# Fri3D_2018_00.net
KiCad netlist of a schematic drawn in Altium Designer
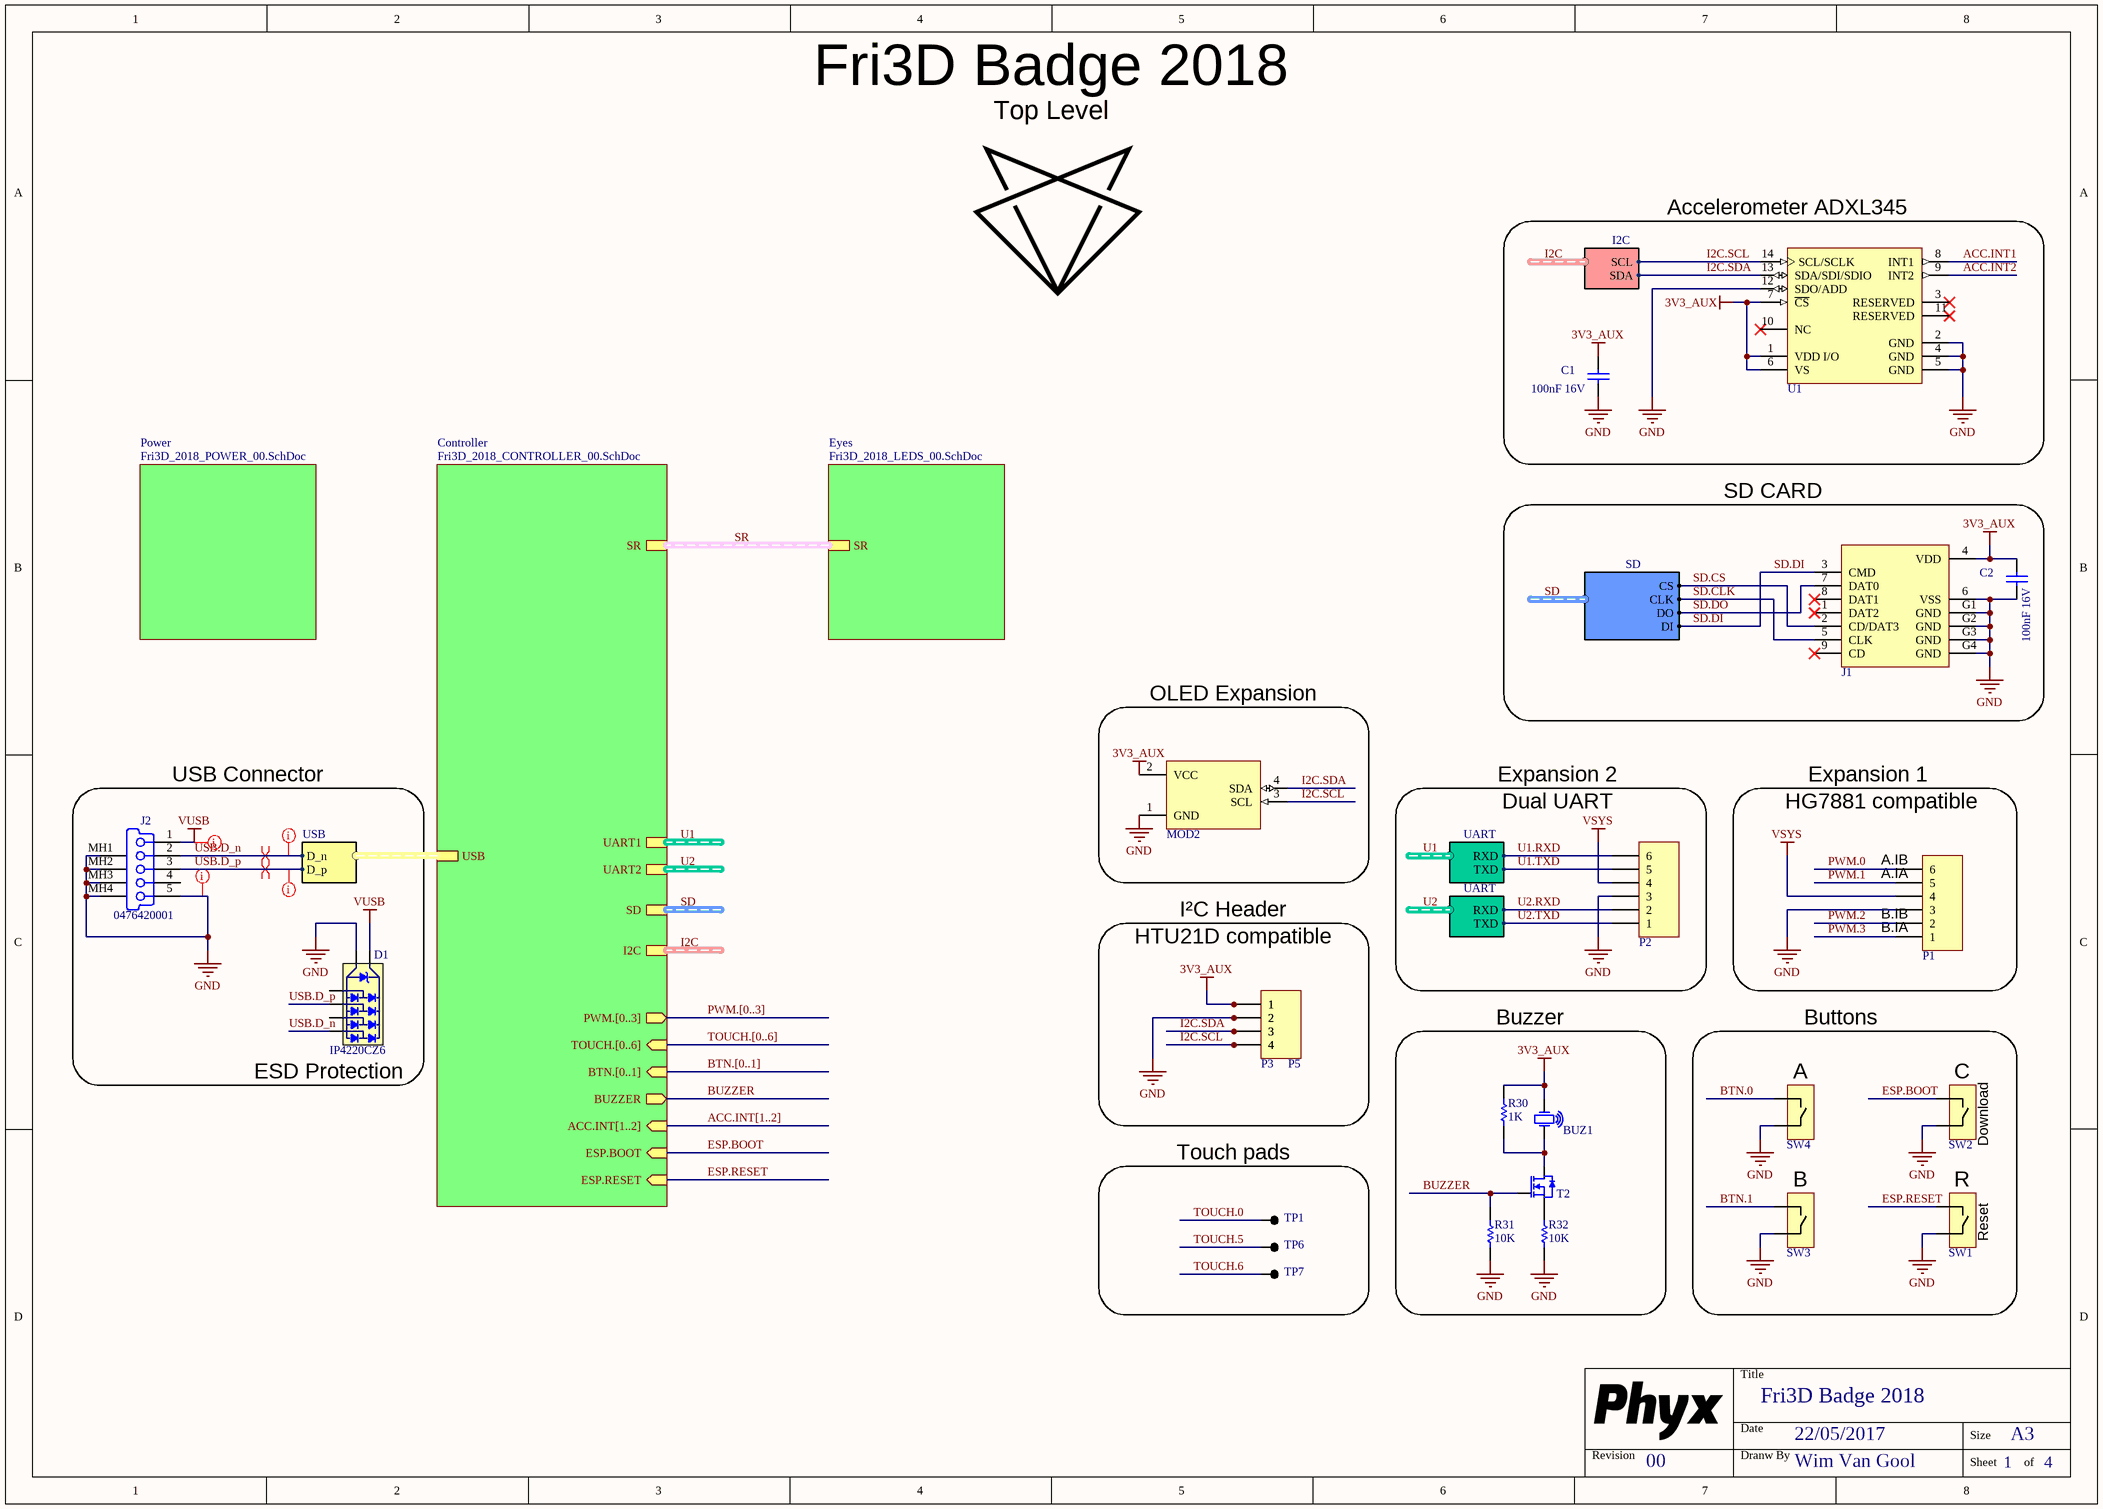
[diagram p0: Fri3D_2018_00.SchDoc]

(export (version "E")
  (design (tool "Eeschema 10.0.6"))
  (components
    (comp (ref "BUZ1")
      (value "12x12x3mm Piezo Buzzer Transducer 81dB")
      (footprint "CUI_CMT-1203-SMT")
      (description "Crystal Oscillator")
      (libsource (lib "Phyx_Components") (part "Buzzer"))
    )
    (comp (ref "C1")
      (value "100nF 16V")
      (footprint "C0603_N")
      (description "Capacitor Ceramic")
      (libsource (lib "Phyx_Components") (part "CAP_CERAMIC"))
    )
    (comp (ref "C2")
      (value "100nF 16V")
      (footprint "C0603_N")
      (description "Capacitor Ceramic")
      (libsource (lib "Phyx_Components") (part "CAP_CERAMIC"))
    )
    (comp (ref "D1")
      (value "IP4220CZ6")
      (footprint "NXP_SOT457")
      (description "=Description")
      (fields (field (name "Comment") "TVS Diode Dual USB"))
      (libsource (lib "Phyx_Components") (part "NXP_IP4220CZ6"))
    )
    (comp (ref "J1")
      (value "Micro SD PiPo Push-Push")
      (footprint "TFP09-2-12B")
      (description "=Description")
      (libsource (lib "Phyx_Components") (part "TFP09-2-12B"))
    )
    (comp (ref "J2")
      (value "0476420001")
      (footprint "MLX_0476420001")
      (fields (field (name "Comment") "Molex 0476420001"))
      (libsource (lib "Phyx_Components") (part "USB_OTG_Mini-B"))
    )
    (comp (ref "MOD2")
      (value "SSD1306 based 128x64 OLED, I2C, module")
      (footprint "OLED_MOD_0.96_I2C")
      (libsource (lib "Phyx_Components") (part "OLED_MOD_0.96_I2C"))
    )
    (comp (ref "P1")
      (value "Header 6")
      (footprint "HDR1X6")
      (libsource (lib "Phyx_Components") (part "Header 6"))
    )
    (comp (ref "P2")
      (value "Header 6")
      (footprint "HDR1X6")
      (libsource (lib "Phyx_Components") (part "Header 6"))
    )
    (comp (ref "P3")
      (value "Header 4")
      (footprint "HDR1X4")
      (libsource (lib "Phyx_Components") (part "Header 4"))
    )
    (comp (ref "P5")
      (value "Header 4")
      (footprint "HDR1X4")
      (libsource (lib "Phyx_Components") (part "Header 4"))
    )
    (comp (ref "R30")
      (value "1K")
      (footprint "R0603_N")
      (libsource (lib "Phyx_Components") (part "RESISTOR"))
    )
    (comp (ref "R31")
      (value "10K")
      (footprint "R0603_N")
      (fields (field (name "Comment") "RESISTOR"))
      (libsource (lib "Phyx_Components") (part "RESISTOR"))
    )
    (comp (ref "R32")
      (value "10K")
      (footprint "R0603_N")
      (fields (field (name "Comment") "RESISTOR"))
      (libsource (lib "Phyx_Components") (part "RESISTOR"))
    )
    (comp (ref "SW1")
      (value "4.5x4.5mm tact SMD H3,8mm")
      (footprint "WE_430181038816")
      (libsource (lib "Phyx_Components") (part "SW_TACT"))
    )
    (comp (ref "SW2")
      (value "4.5x4.5mm tact SMD H3,8mm")
      (footprint "WE_430181038816")
      (libsource (lib "Phyx_Components") (part "SW_TACT"))
    )
    (comp (ref "SW3")
      (value "4.5x4.5mm tact SMD H3,8mm")
      (footprint "WE_430181038816")
      (libsource (lib "Phyx_Components") (part "SW_TACT"))
    )
    (comp (ref "SW4")
      (value "4.5x4.5mm tact SMD H3,8mm")
      (footprint "WE_430181038816")
      (libsource (lib "Phyx_Components") (part "SW_TACT"))
    )
    (comp (ref "T2")
      (value "0.2A N-Ch MOSFET Vgs 3.2")
      (footprint "SOT23-3")
      (libsource (lib "Phyx_Components") (part "N_MOSFET_GSD"))
    )
    (comp (ref "TP1")
      (value "TEST_PAD")
      (footprint "TP_0.8mm")
      (libsource (lib "Phyx_Components") (part "TEST_PAD"))
    )
    (comp (ref "TP6")
      (value "TEST_PAD")
      (footprint "TP_0.8mm")
      (libsource (lib "Phyx_Components") (part "TEST_PAD"))
    )
    (comp (ref "TP7")
      (value "TEST_PAD")
      (footprint "TP_0.8mm")
      (libsource (lib "Phyx_Components") (part "TEST_PAD"))
    )
    (comp (ref "U1")
      (value "3-Axis, ±2 g/±4 g/±8 g/±16 g Digital Accelerometer")
      (footprint "AD_CC-14-1")
      (description "=Description")
      (libsource (lib "Phyx_Components") (part "ADXL345"))
    )
  )
  (nets
    (net (code "15") (name "/ACC.INT1") (class "Default")
      (node (ref "U1") (pin "8") (pinfunction "INT1_8") (pintype "output"))
    )
    (net (code "16") (name "/ACC.INT2") (class "Default")
      (node (ref "U1") (pin "9") (pinfunction "INT2_9") (pintype "output"))
    )
    (net (code "18") (name "/BTN.0") (class "Default")
      (node (ref "SW4") (pin "1") (pinfunction "1_1") (pintype "passive"))
    )
    (net (code "19") (name "/BTN.1") (class "Default")
      (node (ref "SW3") (pin "1") (pinfunction "1_1") (pintype "passive"))
    )
    (net (code "21") (name "/BUZZER") (class "Default")
      (node (ref "R31") (pin "1") (pinfunction "1_1") (pintype "passive"))
      (node (ref "T2") (pin "1") (pinfunction "G_1") (pintype "passive"))
    )
    (net (code "22") (name "/ESP.BOOT") (class "Default")
      (node (ref "SW2") (pin "1") (pinfunction "1_1") (pintype "passive"))
    )
    (net (code "23") (name "/ESP.RESET") (class "Default")
      (node (ref "SW1") (pin "1") (pinfunction "1_1") (pintype "passive"))
    )
    (net (code "24") (name "/I2C.SCL") (class "Default")
      (node (ref "MOD2") (pin "3") (pinfunction "SCL_3") (pintype "input"))
      (node (ref "P3") (pin "4") (pinfunction "4_4") (pintype "passive"))
      (node (ref "P5") (pin "4") (pinfunction "4_4") (pintype "passive"))
      (node (ref "U1") (pin "14") (pinfunction "SCL/SCLK_14") (pintype "input"))
    )
    (net (code "25") (name "/I2C.SDA") (class "Default")
      (node (ref "MOD2") (pin "4") (pinfunction "SDA_4") (pintype "bidirectional"))
      (node (ref "P3") (pin "3") (pinfunction "3_3") (pintype "passive"))
      (node (ref "P5") (pin "3") (pinfunction "3_3") (pintype "passive"))
      (node (ref "U1") (pin "13") (pinfunction "SDA/SDI/SDIO_13") (pintype "bidirectional"))
    )
    (net (code "27") (name "/PWM.0") (class "Default")
      (node (ref "P1") (pin "6") (pinfunction "6_6") (pintype "passive"))
    )
    (net (code "28") (name "/PWM.1") (class "Default")
      (node (ref "P1") (pin "5") (pinfunction "5_5") (pintype "passive"))
    )
    (net (code "29") (name "/PWM.2") (class "Default")
      (node (ref "P1") (pin "2") (pinfunction "2_2") (pintype "passive"))
    )
    (net (code "30") (name "/PWM.3") (class "Default")
      (node (ref "P1") (pin "1") (pinfunction "1_1") (pintype "passive"))
    )
    (net (code "32") (name "/SD.CLK") (class "Default")
      (node (ref "J1") (pin "5") (pinfunction "CLK_5") (pintype "passive"))
    )
    (net (code "33") (name "/SD.CS") (class "Default")
      (node (ref "J1") (pin "2") (pinfunction "CD/DAT3_2") (pintype "passive"))
    )
    (net (code "34") (name "/SD.DI") (class "Default")
      (node (ref "J1") (pin "3") (pinfunction "CMD_3") (pintype "passive"))
    )
    (net (code "35") (name "/SD.DO") (class "Default")
      (node (ref "J1") (pin "7") (pinfunction "DAT0_7") (pintype "passive"))
    )
    (net (code "37") (name "/TOUCH.0") (class "Default")
      (node (ref "TP1") (pin "1") (pinfunction "1_1") (pintype "passive"))
    )
    (net (code "38") (name "/TOUCH.5") (class "Default")
      (node (ref "TP6") (pin "1") (pinfunction "1_1") (pintype "passive"))
    )
    (net (code "39") (name "/TOUCH.6") (class "Default")
      (node (ref "TP7") (pin "1") (pinfunction "1_1") (pintype "passive"))
    )
    (net (code "41") (name "/U1.RXD") (class "Default")
      (node (ref "P2") (pin "6") (pinfunction "6_6") (pintype "passive"))
    )
    (net (code "42") (name "/U1.TXD") (class "Default")
      (node (ref "P2") (pin "5") (pinfunction "5_5") (pintype "passive"))
    )
    (net (code "44") (name "/U2.RXD") (class "Default")
      (node (ref "P2") (pin "2") (pinfunction "2_2") (pintype "passive"))
    )
    (net (code "45") (name "/U2.TXD") (class "Default")
      (node (ref "P2") (pin "1") (pinfunction "1_1") (pintype "passive"))
    )
    (net (code "47") (name "/USB.D_n") (class "Default")
      (node (ref "D1") (pin "6") (pinfunction "6_6") (pintype "passive"))
      (node (ref "J2") (pin "2") (pinfunction "D-_2") (pintype "passive"))
    )
    (net (code "48") (name "/USB.D_p") (class "Default")
      (node (ref "D1") (pin "1") (pinfunction "1_1") (pintype "passive"))
      (node (ref "J2") (pin "3") (pinfunction "D+_3") (pintype "passive"))
    )
    (net (code "55") (name "3V3_AUX") (class "Default")
      (node (ref "BUZ1") (pin "1") (pinfunction "OSC1_1") (pintype "passive"))
      (node (ref "C1") (pin "1") (pinfunction "1_1") (pintype "passive"))
      (node (ref "C2") (pin "1") (pinfunction "1_1") (pintype "passive"))
      (node (ref "J1") (pin "4") (pinfunction "VDD_4") (pintype "power_in"))
      (node (ref "MOD2") (pin "2") (pinfunction "VCC_2") (pintype "power_in"))
      (node (ref "P3") (pin "1") (pinfunction "1_1") (pintype "passive"))
      (node (ref "P5") (pin "1") (pinfunction "1_1") (pintype "passive"))
      (node (ref "R30") (pin "1") (pinfunction "1_1") (pintype "passive"))
      (node (ref "U1") (pin "1") (pinfunction "VDD_I/O_1") (pintype "power_in"))
      (node (ref "U1") (pin "6") (pinfunction "VS_6") (pintype "power_in"))
      (node (ref "U1") (pin "7") (pinfunction "~{CS}_7") (pintype "input"))
    )
    (net (code "56") (name "GND") (class "Default")
      (node (ref "C1") (pin "2") (pinfunction "2_2") (pintype "passive"))
      (node (ref "C2") (pin "2") (pinfunction "2_2") (pintype "passive"))
      (node (ref "D1") (pin "2") (pinfunction "GND_2") (pintype "passive"))
      (node (ref "J1") (pin "6") (pinfunction "VSS_6") (pintype "power_in"))
      (node (ref "J1") (pin "G1") (pinfunction "GND_G1") (pintype "power_in"))
      (node (ref "J1") (pin "G2") (pinfunction "GND_G2") (pintype "power_in"))
      (node (ref "J1") (pin "G3") (pinfunction "GND_G3") (pintype "power_in"))
      (node (ref "J1") (pin "G4") (pinfunction "GND_G4") (pintype "power_in"))
      (node (ref "J2") (pin "5") (pinfunction "GND_5") (pintype "passive"))
      (node (ref "J2") (pin "MH1") (pinfunction "Tab_MH1") (pintype "passive"))
      (node (ref "J2") (pin "MH2") (pinfunction "Tab_MH2") (pintype "passive"))
      (node (ref "J2") (pin "MH3") (pinfunction "Tab_MH3") (pintype "passive"))
      (node (ref "J2") (pin "MH4") (pinfunction "Tab_MH4") (pintype "passive"))
      (node (ref "MOD2") (pin "1") (pinfunction "GND_1") (pintype "power_in"))
      (node (ref "P1") (pin "3") (pinfunction "3_3") (pintype "passive"))
      (node (ref "P2") (pin "3") (pinfunction "3_3") (pintype "passive"))
      (node (ref "P3") (pin "2") (pinfunction "2_2") (pintype "passive"))
      (node (ref "P5") (pin "2") (pinfunction "2_2") (pintype "passive"))
      (node (ref "R31") (pin "2") (pinfunction "2_2") (pintype "passive"))
      (node (ref "R32") (pin "2") (pinfunction "2_2") (pintype "passive"))
      (node (ref "SW1") (pin "2") (pinfunction "2_2") (pintype "passive"))
      (node (ref "SW2") (pin "2") (pinfunction "2_2") (pintype "passive"))
      (node (ref "SW3") (pin "2") (pinfunction "2_2") (pintype "passive"))
      (node (ref "SW4") (pin "2") (pinfunction "2_2") (pintype "passive"))
      (node (ref "U1") (pin "12") (pinfunction "SDO/ADD_12") (pintype "bidirectional"))
      (node (ref "U1") (pin "2") (pinfunction "GND_2") (pintype "power_in"))
      (node (ref "U1") (pin "4") (pinfunction "GND_4") (pintype "power_in"))
      (node (ref "U1") (pin "5") (pinfunction "GND_5") (pintype "power_in"))
    )
    (net (code "57") (name "Net-(BUZ1-OSC2)") (class "Default")
      (node (ref "BUZ1") (pin "2") (pinfunction "OSC2_2") (pintype "passive"))
      (node (ref "R30") (pin "2") (pinfunction "2_2") (pintype "passive"))
      (node (ref "T2") (pin "3") (pinfunction "D_3") (pintype "passive"))
    )
    (net (code "58") (name "Net-(T2-S)") (class "Default")
      (node (ref "R32") (pin "1") (pinfunction "1_1") (pintype "passive"))
      (node (ref "T2") (pin "2") (pinfunction "S_2") (pintype "passive"))
    )
    (net (code "59") (name "VSYS") (class "Default")
      (node (ref "P1") (pin "4") (pinfunction "4_4") (pintype "passive"))
      (node (ref "P2") (pin "4") (pinfunction "4_4") (pintype "passive"))
    )
    (net (code "60") (name "VUSB") (class "Default")
      (node (ref "D1") (pin "5") (pinfunction "VBus_5") (pintype "passive"))
      (node (ref "J2") (pin "1") (pinfunction "V_BUS_(5V)_1") (pintype "passive"))
    )
    (net (code "61") (name "unconnected-(D1-Pad3)") (class "Default")
      (node (ref "D1") (pin "3") (pinfunction "3_3") (pintype "passive"))
    )
    (net (code "62") (name "unconnected-(D1-Pad4)") (class "Default")
      (node (ref "D1") (pin "4") (pinfunction "4_4") (pintype "passive"))
    )
    (net (code "63") (name "unconnected-(J1-CD-Pad9)") (class "Default")
      (node (ref "J1") (pin "9") (pinfunction "CD_9") (pintype "passive+no_connect"))
    )
    (net (code "64") (name "unconnected-(J1-DAT1-Pad8)") (class "Default")
      (node (ref "J1") (pin "8") (pinfunction "DAT1_8") (pintype "passive+no_connect"))
    )
    (net (code "65") (name "unconnected-(J1-DAT2-Pad1)") (class "Default")
      (node (ref "J1") (pin "1") (pinfunction "DAT2_1") (pintype "passive+no_connect"))
    )
    (net (code "66") (name "unconnected-(J2-NC-Pad4)") (class "Default")
      (node (ref "J2") (pin "4") (pinfunction "NC_4") (pintype "passive"))
    )
    (net (code "67") (name "unconnected-(U1-NC-Pad10)") (class "Default")
      (node (ref "U1") (pin "10") (pinfunction "NC_10") (pintype "passive+no_connect"))
    )
    (net (code "68") (name "unconnected-(U1-RESERVED-Pad3)") (class "Default")
      (node (ref "U1") (pin "3") (pinfunction "RESERVED_3") (pintype "passive+no_connect"))
    )
    (net (code "69") (name "unconnected-(U1-RESERVED-Pad11)") (class "Default")
      (node (ref "U1") (pin "11") (pinfunction "RESERVED_11") (pintype "passive+no_connect"))
    )
  )
)
